# ElekShemaRelais.net
KiCad netlist of a schematic drawn in Altium Designer
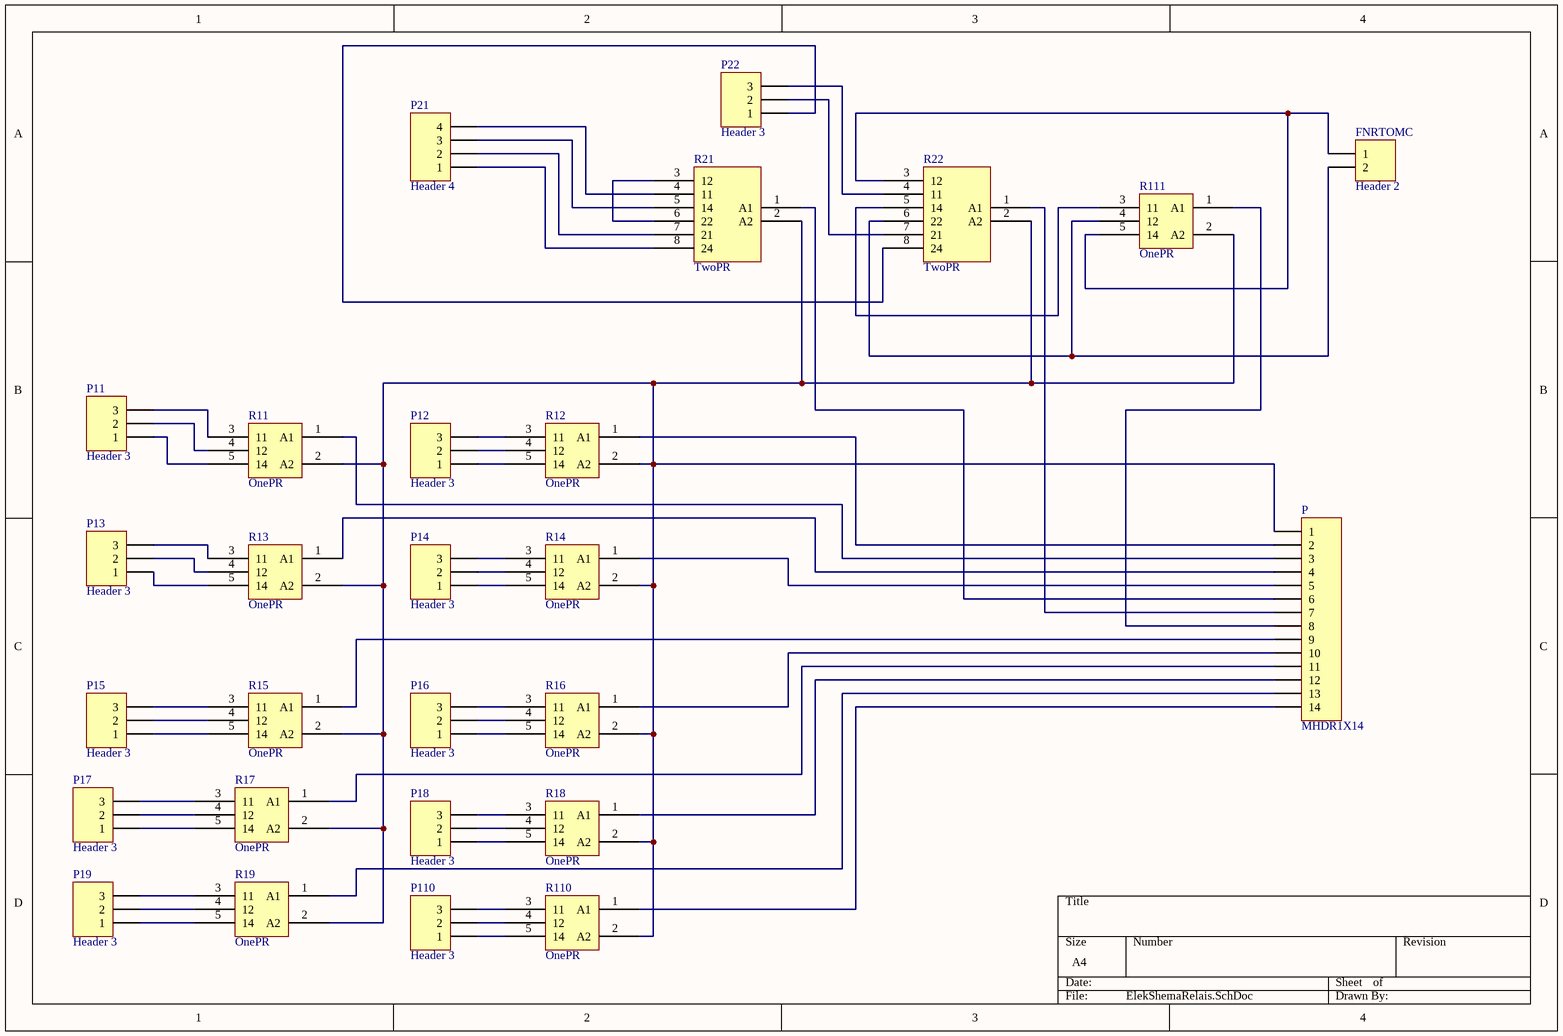
[diagram p0: ElekShemaRelais.SchDoc]

(export (version "E")
  (design (tool "Eeschema 10.0.6"))
  (components
    (comp (ref "FNRTOMC")
      (value "Header 2")
      (footprint "HDR2")
      (description "Header, 2-Pin")
      (fields (field (name "PUBLISHER") "Altium Limited"))
      (libsource (lib "Miscellaneous Connectors") (part "Header 2"))
    )
    (comp (ref "P")
      (value "MHDR1X14")
      (footprint "HDR14")
      (description "Header, 14-Pin")
      (fields (field (name "PUBLISHER") "Altium Limited"))
      (libsource (lib "Miscellaneous Connectors") (part "MHDR1X14"))
    )
    (comp (ref "P11")
      (value "Header 3")
      (footprint "HDR3")
      (description "Header, 3-Pin")
      (fields (field (name "PUBLISHER") "Altium Limited"))
      (libsource (lib "Miscellaneous Connectors") (part "Header 3"))
    )
    (comp (ref "P12")
      (value "Header 3")
      (footprint "HDR3")
      (description "Header, 3-Pin")
      (fields (field (name "PUBLISHER") "Altium Limited"))
      (libsource (lib "Miscellaneous Connectors") (part "Header 3"))
    )
    (comp (ref "P13")
      (value "Header 3")
      (footprint "HDR3")
      (description "Header, 3-Pin")
      (fields (field (name "PUBLISHER") "Altium Limited"))
      (libsource (lib "Miscellaneous Connectors") (part "Header 3"))
    )
    (comp (ref "P14")
      (value "Header 3")
      (footprint "HDR3")
      (description "Header, 3-Pin")
      (fields (field (name "PUBLISHER") "Altium Limited"))
      (libsource (lib "Miscellaneous Connectors") (part "Header 3"))
    )
    (comp (ref "P15")
      (value "Header 3")
      (footprint "HDR3")
      (description "Header, 3-Pin")
      (fields (field (name "PUBLISHER") "Altium Limited"))
      (libsource (lib "Miscellaneous Connectors") (part "Header 3"))
    )
    (comp (ref "P16")
      (value "Header 3")
      (footprint "HDR3")
      (description "Header, 3-Pin")
      (fields (field (name "PUBLISHER") "Altium Limited"))
      (libsource (lib "Miscellaneous Connectors") (part "Header 3"))
    )
    (comp (ref "P17")
      (value "Header 3")
      (footprint "HDR3")
      (description "Header, 3-Pin")
      (fields (field (name "PUBLISHER") "Altium Limited"))
      (libsource (lib "Miscellaneous Connectors") (part "Header 3"))
    )
    (comp (ref "P18")
      (value "Header 3")
      (footprint "HDR3")
      (description "Header, 3-Pin")
      (fields (field (name "PUBLISHER") "Altium Limited"))
      (libsource (lib "Miscellaneous Connectors") (part "Header 3"))
    )
    (comp (ref "P19")
      (value "Header 3")
      (footprint "HDR3")
      (description "Header, 3-Pin")
      (fields (field (name "PUBLISHER") "Altium Limited"))
      (libsource (lib "Miscellaneous Connectors") (part "Header 3"))
    )
    (comp (ref "P21")
      (value "Header 4")
      (footprint "HDR4")
      (description "Header, 4-Pin")
      (fields (field (name "PUBLISHER") "Altium Limited"))
      (libsource (lib "Miscellaneous Connectors") (part "Header 4"))
    )
    (comp (ref "P22")
      (value "Header 3")
      (footprint "HDR3")
      (description "Header, 3-Pin")
      (fields (field (name "PUBLISHER") "Altium Limited"))
      (libsource (lib "Miscellaneous Connectors") (part "Header 3"))
    )
    (comp (ref "P110")
      (value "Header 3")
      (footprint "HDR3")
      (description "Header, 3-Pin")
      (fields (field (name "PUBLISHER") "Altium Limited"))
      (libsource (lib "Miscellaneous Connectors") (part "Header 3"))
    )
    (comp (ref "R11") (value "OnePR") (footprint "EENPOOL") (libsource (lib "Schlib1") (part "R1")))
    (comp (ref "R12") (value "OnePR") (footprint "EENPOOL") (libsource (lib "Schlib1") (part "R1")))
    (comp (ref "R13") (value "OnePR") (footprint "EENPOOL") (libsource (lib "Schlib1") (part "R1")))
    (comp (ref "R14") (value "OnePR") (footprint "EENPOOL") (libsource (lib "Schlib1") (part "R1")))
    (comp (ref "R15") (value "OnePR") (footprint "EENPOOL") (libsource (lib "Schlib1") (part "R1")))
    (comp (ref "R16") (value "OnePR") (footprint "EENPOOL") (libsource (lib "Schlib1") (part "R1")))
    (comp (ref "R17") (value "OnePR") (footprint "EENPOOL") (libsource (lib "Schlib1") (part "R1")))
    (comp (ref "R18") (value "OnePR") (footprint "EENPOOL") (libsource (lib "Schlib1") (part "R1")))
    (comp (ref "R19") (value "OnePR") (footprint "EENPOOL") (libsource (lib "Schlib1") (part "R1")))
    (comp (ref "R21") (value "TwoPR") (footprint "TWEEPOOL") (libsource (lib "Schlib1") (part "R2")))
    (comp (ref "R22") (value "TwoPR") (footprint "TWEEPOOL") (libsource (lib "Schlib1") (part "R2")))
    (comp (ref "R110") (value "OnePR") (footprint "EENPOOL") (libsource (lib "Schlib1") (part "R1")))
    (comp (ref "R111") (value "OnePR") (footprint "EENPOOL") (libsource (lib "Schlib1") (part "R1")))
  )
  (nets
    (net (code "1") (name "Net-(R11-11)") (class "Default")
      (node (ref "P11") (pin "3") (pinfunction "3_3") (pintype "passive"))
      (node (ref "R11") (pin "3") (pinfunction "11_3") (pintype "passive"))
    )
    (net (code "2") (name "Net-(R11-12)") (class "Default")
      (node (ref "P11") (pin "2") (pinfunction "2_2") (pintype "passive"))
      (node (ref "R11") (pin "4") (pinfunction "12_4") (pintype "passive"))
    )
    (net (code "3") (name "Net-(R11-14)") (class "Default")
      (node (ref "P11") (pin "1") (pinfunction "1_1") (pintype "passive"))
      (node (ref "R11") (pin "5") (pinfunction "14_5") (pintype "passive"))
    )
    (net (code "4") (name "Net-(R11-A1)") (class "Default")
      (node (ref "P") (pin "3") (pinfunction "3_3") (pintype "passive"))
      (node (ref "R11") (pin "1") (pinfunction "A1_1") (pintype "passive"))
    )
    (net (code "5") (name "Net-(R11-A2)") (class "Default")
      (node (ref "P") (pin "1") (pinfunction "1_1") (pintype "passive"))
      (node (ref "R11") (pin "2") (pinfunction "A2_2") (pintype "passive"))
      (node (ref "R110") (pin "2") (pinfunction "A2_2") (pintype "passive"))
      (node (ref "R111") (pin "2") (pinfunction "A2_2") (pintype "passive"))
      (node (ref "R12") (pin "2") (pinfunction "A2_2") (pintype "passive"))
      (node (ref "R13") (pin "2") (pinfunction "A2_2") (pintype "passive"))
      (node (ref "R14") (pin "2") (pinfunction "A2_2") (pintype "passive"))
      (node (ref "R15") (pin "2") (pinfunction "A2_2") (pintype "passive"))
      (node (ref "R16") (pin "2") (pinfunction "A2_2") (pintype "passive"))
      (node (ref "R17") (pin "2") (pinfunction "A2_2") (pintype "passive"))
      (node (ref "R18") (pin "2") (pinfunction "A2_2") (pintype "passive"))
      (node (ref "R19") (pin "2") (pinfunction "A2_2") (pintype "passive"))
      (node (ref "R21") (pin "2") (pinfunction "A2_2") (pintype "passive"))
      (node (ref "R22") (pin "2") (pinfunction "A2_2") (pintype "passive"))
    )
    (net (code "6") (name "Net-(R12-11)") (class "Default")
      (node (ref "P12") (pin "3") (pinfunction "3_3") (pintype "passive"))
      (node (ref "R12") (pin "3") (pinfunction "11_3") (pintype "passive"))
    )
    (net (code "7") (name "Net-(R12-12)") (class "Default")
      (node (ref "P12") (pin "2") (pinfunction "2_2") (pintype "passive"))
      (node (ref "R12") (pin "4") (pinfunction "12_4") (pintype "passive"))
    )
    (net (code "8") (name "Net-(R12-14)") (class "Default")
      (node (ref "P12") (pin "1") (pinfunction "1_1") (pintype "passive"))
      (node (ref "R12") (pin "5") (pinfunction "14_5") (pintype "passive"))
    )
    (net (code "9") (name "Net-(R12-A1)") (class "Default")
      (node (ref "P") (pin "2") (pinfunction "2_2") (pintype "passive"))
      (node (ref "R12") (pin "1") (pinfunction "A1_1") (pintype "passive"))
    )
    (net (code "10") (name "Net-(R13-11)") (class "Default")
      (node (ref "P13") (pin "3") (pinfunction "3_3") (pintype "passive"))
      (node (ref "R13") (pin "3") (pinfunction "11_3") (pintype "passive"))
    )
    (net (code "11") (name "Net-(R13-12)") (class "Default")
      (node (ref "P13") (pin "2") (pinfunction "2_2") (pintype "passive"))
      (node (ref "R13") (pin "4") (pinfunction "12_4") (pintype "passive"))
    )
    (net (code "12") (name "Net-(R13-14)") (class "Default")
      (node (ref "P13") (pin "1") (pinfunction "1_1") (pintype "passive"))
      (node (ref "R13") (pin "5") (pinfunction "14_5") (pintype "passive"))
    )
    (net (code "13") (name "Net-(R13-A1)") (class "Default")
      (node (ref "P") (pin "4") (pinfunction "4_4") (pintype "passive"))
      (node (ref "R13") (pin "1") (pinfunction "A1_1") (pintype "passive"))
    )
    (net (code "14") (name "Net-(R14-11)") (class "Default")
      (node (ref "P14") (pin "3") (pinfunction "3_3") (pintype "passive"))
      (node (ref "R14") (pin "3") (pinfunction "11_3") (pintype "passive"))
    )
    (net (code "15") (name "Net-(R14-12)") (class "Default")
      (node (ref "P14") (pin "2") (pinfunction "2_2") (pintype "passive"))
      (node (ref "R14") (pin "4") (pinfunction "12_4") (pintype "passive"))
    )
    (net (code "16") (name "Net-(R14-14)") (class "Default")
      (node (ref "P14") (pin "1") (pinfunction "1_1") (pintype "passive"))
      (node (ref "R14") (pin "5") (pinfunction "14_5") (pintype "passive"))
    )
    (net (code "17") (name "Net-(R14-A1)") (class "Default")
      (node (ref "P") (pin "5") (pinfunction "5_5") (pintype "passive"))
      (node (ref "R14") (pin "1") (pinfunction "A1_1") (pintype "passive"))
    )
    (net (code "18") (name "Net-(R15-11)") (class "Default")
      (node (ref "P15") (pin "3") (pinfunction "3_3") (pintype "passive"))
      (node (ref "R15") (pin "3") (pinfunction "11_3") (pintype "passive"))
    )
    (net (code "19") (name "Net-(R15-12)") (class "Default")
      (node (ref "P15") (pin "2") (pinfunction "2_2") (pintype "passive"))
      (node (ref "R15") (pin "4") (pinfunction "12_4") (pintype "passive"))
    )
    (net (code "20") (name "Net-(R15-14)") (class "Default")
      (node (ref "P15") (pin "1") (pinfunction "1_1") (pintype "passive"))
      (node (ref "R15") (pin "5") (pinfunction "14_5") (pintype "passive"))
    )
    (net (code "21") (name "Net-(R15-A1)") (class "Default")
      (node (ref "P") (pin "9") (pinfunction "9_9") (pintype "passive"))
      (node (ref "R15") (pin "1") (pinfunction "A1_1") (pintype "passive"))
    )
    (net (code "22") (name "Net-(R16-11)") (class "Default")
      (node (ref "P16") (pin "3") (pinfunction "3_3") (pintype "passive"))
      (node (ref "R16") (pin "3") (pinfunction "11_3") (pintype "passive"))
    )
    (net (code "23") (name "Net-(R16-12)") (class "Default")
      (node (ref "P16") (pin "2") (pinfunction "2_2") (pintype "passive"))
      (node (ref "R16") (pin "4") (pinfunction "12_4") (pintype "passive"))
    )
    (net (code "24") (name "Net-(R16-14)") (class "Default")
      (node (ref "P16") (pin "1") (pinfunction "1_1") (pintype "passive"))
      (node (ref "R16") (pin "5") (pinfunction "14_5") (pintype "passive"))
    )
    (net (code "25") (name "Net-(R16-A1)") (class "Default")
      (node (ref "P") (pin "10") (pinfunction "10_10") (pintype "passive"))
      (node (ref "R16") (pin "1") (pinfunction "A1_1") (pintype "passive"))
    )
    (net (code "26") (name "Net-(R17-11)") (class "Default")
      (node (ref "P17") (pin "3") (pinfunction "3_3") (pintype "passive"))
      (node (ref "R17") (pin "3") (pinfunction "11_3") (pintype "passive"))
    )
    (net (code "27") (name "Net-(R17-12)") (class "Default")
      (node (ref "P17") (pin "2") (pinfunction "2_2") (pintype "passive"))
      (node (ref "R17") (pin "4") (pinfunction "12_4") (pintype "passive"))
    )
    (net (code "28") (name "Net-(R17-14)") (class "Default")
      (node (ref "P17") (pin "1") (pinfunction "1_1") (pintype "passive"))
      (node (ref "R17") (pin "5") (pinfunction "14_5") (pintype "passive"))
    )
    (net (code "29") (name "Net-(R17-A1)") (class "Default")
      (node (ref "P") (pin "11") (pinfunction "11_11") (pintype "passive"))
      (node (ref "R17") (pin "1") (pinfunction "A1_1") (pintype "passive"))
    )
    (net (code "30") (name "Net-(R18-11)") (class "Default")
      (node (ref "P18") (pin "3") (pinfunction "3_3") (pintype "passive"))
      (node (ref "R18") (pin "3") (pinfunction "11_3") (pintype "passive"))
    )
    (net (code "31") (name "Net-(R18-12)") (class "Default")
      (node (ref "P18") (pin "2") (pinfunction "2_2") (pintype "passive"))
      (node (ref "R18") (pin "4") (pinfunction "12_4") (pintype "passive"))
    )
    (net (code "32") (name "Net-(R18-14)") (class "Default")
      (node (ref "P18") (pin "1") (pinfunction "1_1") (pintype "passive"))
      (node (ref "R18") (pin "5") (pinfunction "14_5") (pintype "passive"))
    )
    (net (code "33") (name "Net-(R18-A1)") (class "Default")
      (node (ref "P") (pin "12") (pinfunction "12_12") (pintype "passive"))
      (node (ref "R18") (pin "1") (pinfunction "A1_1") (pintype "passive"))
    )
    (net (code "34") (name "Net-(R19-11)") (class "Default")
      (node (ref "P19") (pin "3") (pinfunction "3_3") (pintype "passive"))
      (node (ref "R19") (pin "3") (pinfunction "11_3") (pintype "passive"))
    )
    (net (code "35") (name "Net-(R19-12)") (class "Default")
      (node (ref "P19") (pin "2") (pinfunction "2_2") (pintype "passive"))
      (node (ref "R19") (pin "4") (pinfunction "12_4") (pintype "passive"))
    )
    (net (code "36") (name "Net-(R19-14)") (class "Default")
      (node (ref "P19") (pin "1") (pinfunction "1_1") (pintype "passive"))
      (node (ref "R19") (pin "5") (pinfunction "14_5") (pintype "passive"))
    )
    (net (code "37") (name "Net-(R19-A1)") (class "Default")
      (node (ref "P") (pin "13") (pinfunction "13_13") (pintype "passive"))
      (node (ref "R19") (pin "1") (pinfunction "A1_1") (pintype "passive"))
    )
    (net (code "38") (name "Net-(R21-11)") (class "Default")
      (node (ref "P21") (pin "4") (pinfunction "4_4") (pintype "passive"))
      (node (ref "R21") (pin "4") (pinfunction "11_4") (pintype "passive"))
    )
    (net (code "39") (name "Net-(R21-12)") (class "Default")
      (node (ref "R21") (pin "3") (pinfunction "12_3") (pintype "passive"))
      (node (ref "R21") (pin "6") (pinfunction "22_6") (pintype "passive"))
    )
    (net (code "40") (name "Net-(R21-14)") (class "Default")
      (node (ref "P21") (pin "3") (pinfunction "3_3") (pintype "passive"))
      (node (ref "R21") (pin "5") (pinfunction "14_5") (pintype "passive"))
    )
    (net (code "41") (name "Net-(R21-21)") (class "Default")
      (node (ref "P21") (pin "2") (pinfunction "2_2") (pintype "passive"))
      (node (ref "R21") (pin "7") (pinfunction "21_7") (pintype "passive"))
    )
    (net (code "42") (name "Net-(R21-24)") (class "Default")
      (node (ref "P21") (pin "1") (pinfunction "1_1") (pintype "passive"))
      (node (ref "R21") (pin "8") (pinfunction "24_8") (pintype "passive"))
    )
    (net (code "43") (name "Net-(R21-A1)") (class "Default")
      (node (ref "P") (pin "6") (pinfunction "6_6") (pintype "passive"))
      (node (ref "R21") (pin "1") (pinfunction "A1_1") (pintype "passive"))
    )
    (net (code "44") (name "Net-(R22-11)") (class "Default")
      (node (ref "P22") (pin "3") (pinfunction "3_3") (pintype "passive"))
      (node (ref "R22") (pin "4") (pinfunction "11_4") (pintype "passive"))
    )
    (net (code "45") (name "Net-(R22-21)") (class "Default")
      (node (ref "P22") (pin "2") (pinfunction "2_2") (pintype "passive"))
      (node (ref "R22") (pin "7") (pinfunction "21_7") (pintype "passive"))
    )
    (net (code "46") (name "Net-(R22-24)") (class "Default")
      (node (ref "P22") (pin "1") (pinfunction "1_1") (pintype "passive"))
      (node (ref "R22") (pin "8") (pinfunction "24_8") (pintype "passive"))
    )
    (net (code "47") (name "Net-(R22-A1)") (class "Default")
      (node (ref "P") (pin "7") (pinfunction "7_7") (pintype "passive"))
      (node (ref "R22") (pin "1") (pinfunction "A1_1") (pintype "passive"))
    )
    (net (code "48") (name "Net-(R110-11)") (class "Default")
      (node (ref "P110") (pin "3") (pinfunction "3_3") (pintype "passive"))
      (node (ref "R110") (pin "3") (pinfunction "11_3") (pintype "passive"))
    )
    (net (code "49") (name "Net-(R110-12)") (class "Default")
      (node (ref "P110") (pin "2") (pinfunction "2_2") (pintype "passive"))
      (node (ref "R110") (pin "4") (pinfunction "12_4") (pintype "passive"))
    )
    (net (code "50") (name "Net-(R110-14)") (class "Default")
      (node (ref "P110") (pin "1") (pinfunction "1_1") (pintype "passive"))
      (node (ref "R110") (pin "5") (pinfunction "14_5") (pintype "passive"))
    )
    (net (code "51") (name "Net-(R110-A1)") (class "Default")
      (node (ref "P") (pin "14") (pinfunction "14_14") (pintype "passive"))
      (node (ref "R110") (pin "1") (pinfunction "A1_1") (pintype "passive"))
    )
    (net (code "52") (name "Net-(R111-11)") (class "Default")
      (node (ref "R111") (pin "3") (pinfunction "11_3") (pintype "passive"))
      (node (ref "R22") (pin "5") (pinfunction "14_5") (pintype "passive"))
    )
    (net (code "53") (name "Net-(R111-12)") (class "Default")
      (node (ref "FNRTOMC") (pin "2") (pinfunction "2_2") (pintype "passive"))
      (node (ref "R111") (pin "4") (pinfunction "12_4") (pintype "passive"))
      (node (ref "R22") (pin "6") (pinfunction "22_6") (pintype "passive"))
    )
    (net (code "54") (name "Net-(R111-14)") (class "Default")
      (node (ref "FNRTOMC") (pin "1") (pinfunction "1_1") (pintype "passive"))
      (node (ref "R111") (pin "5") (pinfunction "14_5") (pintype "passive"))
      (node (ref "R22") (pin "3") (pinfunction "12_3") (pintype "passive"))
    )
    (net (code "55") (name "Net-(R111-A1)") (class "Default")
      (node (ref "P") (pin "8") (pinfunction "8_8") (pintype "passive"))
      (node (ref "R111") (pin "1") (pinfunction "A1_1") (pintype "passive"))
    )
  )
)
